# spoke.net
KiCad netlist of a schematic drawn in EAGLE
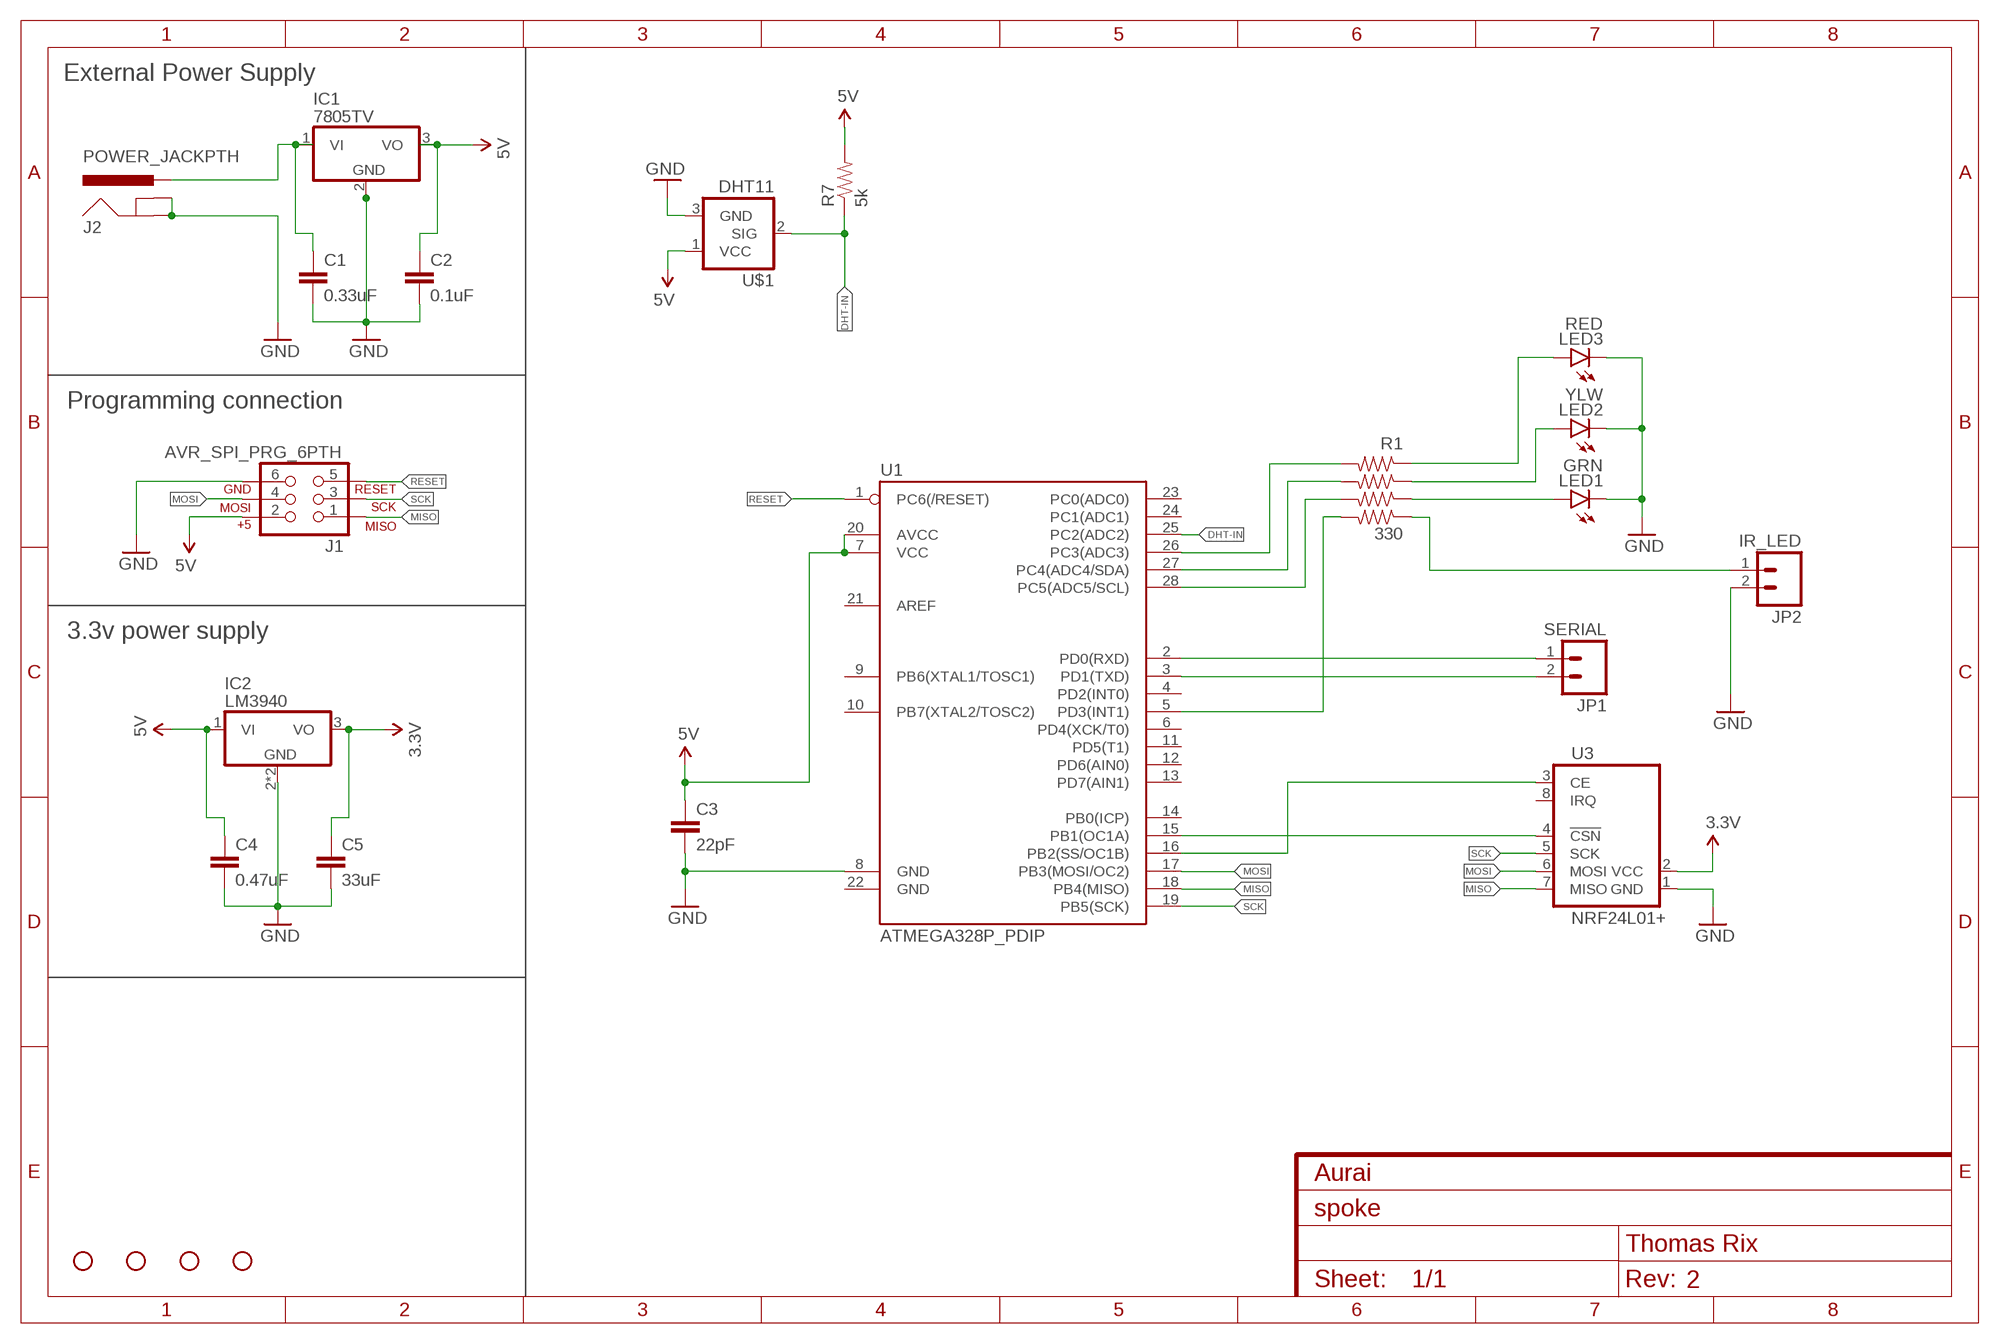
[diagram p0: schematic, sheet 1]

(export (version "E")
  (design (tool "Eeschema 10.0.6"))
  (components
    (comp (ref "C1")
      (value "0.33uF")
      (footprint "eagle-import:0805")
      (libsource (lib "eagle-import") (part "CAP0805"))
    )
    (comp (ref "C2")
      (value "0.1uF")
      (footprint "eagle-import:0805")
      (libsource (lib "eagle-import") (part "CAP0805"))
    )
    (comp (ref "C3")
      (value "22pF")
      (footprint "eagle-import:0805")
      (libsource (lib "eagle-import") (part "SparkFun-Passives_CAP0805"))
    )
    (comp (ref "C4")
      (value "0.47uF")
      (footprint "eagle-import:0805")
      (libsource (lib "eagle-import") (part "CAP0805"))
    )
    (comp (ref "C5")
      (value "33uF")
      (footprint "eagle-import:0805")
      (libsource (lib "eagle-import") (part "CAP0805"))
    )
    (comp (ref "IC1")
      (value "7805TV")
      (footprint "eagle-import:TO220V")
      (libsource (lib "eagle-import") (part "78TV05"))
    )
    (comp (ref "IC2")
      (value "LM3940")
      (footprint "eagle-import:SOT223")
      (libsource (lib "eagle-import") (part "LM3940"))
    )
    (comp (ref "J1")
      (value "AVR_SPI_PRG_6PTH")
      (footprint "eagle-import:2X3")
      (libsource (lib "eagle-import") (part "AVR_SPI_PRG_6PTH"))
    )
    (comp (ref "J2")
      (value "POWER_JACKPTH")
      (footprint "eagle-import:POWER_JACK_PTH")
      (libsource (lib "eagle-import") (part "POWER_JACKPTH"))
    )
    (comp (ref "JP1")
      (value "SERIAL")
      (footprint "eagle-import:1X02")
      (libsource (lib "eagle-import") (part "M02PTH"))
    )
    (comp (ref "JP2")
      (value "IR_LED")
      (footprint "eagle-import:1X02")
      (libsource (lib "eagle-import") (part "M02PTH"))
    )
    (comp (ref "LED1")
      (value "GRN")
      (footprint "eagle-import:LED-1206")
      (libsource (lib "eagle-import") (part "LED1206"))
    )
    (comp (ref "LED2")
      (value "YLW")
      (footprint "eagle-import:LED-1206")
      (libsource (lib "eagle-import") (part "LED1206"))
    )
    (comp (ref "LED3")
      (value "RED")
      (footprint "eagle-import:LED-1206")
      (libsource (lib "eagle-import") (part "LED1206"))
    )
    (comp (ref "R1")
      (value "330")
      (footprint "eagle-import:CRA06S08")
      (libsource (lib "eagle-import") (part "CRA06ES08"))
    )
    (comp (ref "R7")
      (value "5k")
      (footprint "eagle-import:0805")
      (libsource (lib "eagle-import") (part "RESISTOR0805-RES"))
    )
    (comp (ref "STANDOFF1")
      (value "STAND-OFF")
      (footprint "eagle-import:STAND-OFF")
      (libsource (lib "eagle-import") (part "STAND-OFF"))
    )
    (comp (ref "STANDOFF2")
      (value "STAND-OFF")
      (footprint "eagle-import:STAND-OFF")
      (libsource (lib "eagle-import") (part "STAND-OFF"))
    )
    (comp (ref "STANDOFF3")
      (value "STAND-OFF")
      (footprint "eagle-import:STAND-OFF")
      (libsource (lib "eagle-import") (part "STAND-OFF"))
    )
    (comp (ref "STANDOFF4")
      (value "STAND-OFF")
      (footprint "eagle-import:STAND-OFF")
      (libsource (lib "eagle-import") (part "STAND-OFF"))
    )
    (comp (ref "U$1")
      (value "DHT11")
      (footprint "eagle-import:DHT11_HEADER")
      (libsource (lib "eagle-import") (part "DHT11"))
    )
    (comp (ref "U1")
      (value "ATMEGA328P_PDIP")
      (footprint "eagle-import:DIL28-3")
      (libsource (lib "eagle-import") (part "ATMEGA328P_PDIP"))
    )
    (comp (ref "U3")
      (value "NRF24L01+")
      (footprint "eagle-import:NRF24L01_HEADER")
      (libsource (lib "eagle-import") (part "NRF24L01+"))
    )
  )
  (nets
    (net (code "1") (name "3.3V") (class "Default")
      (node (ref "C5") (pin "1") (pinfunction "1_1") (pintype "passive"))
      (node (ref "IC2") (pin "3") (pinfunction "VO_3") (pintype "passive"))
      (node (ref "U3") (pin "2") (pinfunction "VCC_2") (pintype "power_in"))
    )
    (net (code "2") (name "5V") (class "Default")
      (node (ref "C2") (pin "1") (pinfunction "1_1") (pintype "passive"))
      (node (ref "C3") (pin "1") (pinfunction "1_1") (pintype "passive"))
      (node (ref "C4") (pin "1") (pinfunction "1_1") (pintype "passive"))
      (node (ref "IC1") (pin "3") (pinfunction "VO_3") (pintype "passive"))
      (node (ref "IC2") (pin "1") (pinfunction "VI_1") (pintype "input"))
      (node (ref "J1") (pin "2") (pinfunction "2_2") (pintype "passive"))
      (node (ref "R7") (pin "2") (pinfunction "2_2") (pintype "passive"))
      (node (ref "U$1") (pin "1") (pinfunction "VCC_1") (pintype "power_in"))
      (node (ref "U1") (pin "20") (pinfunction "AVCC_20") (pintype "bidirectional"))
      (node (ref "U1") (pin "7") (pinfunction "VCC_7") (pintype "bidirectional"))
    )
    (net (code "3") (name "DHT-IN") (class "Default")
      (node (ref "R7") (pin "1") (pinfunction "1_1") (pintype "passive"))
      (node (ref "U$1") (pin "2") (pinfunction "SIG_2") (pintype "bidirectional"))
      (node (ref "U1") (pin "25") (pinfunction "PC2(ADC2)_25") (pintype "bidirectional"))
    )
    (net (code "4") (name "GND") (class "Default")
      (node (ref "C1") (pin "2") (pinfunction "2_2") (pintype "passive"))
      (node (ref "C2") (pin "2") (pinfunction "2_2") (pintype "passive"))
      (node (ref "C3") (pin "2") (pinfunction "2_2") (pintype "passive"))
      (node (ref "C4") (pin "2") (pinfunction "2_2") (pintype "passive"))
      (node (ref "C5") (pin "2") (pinfunction "2_2") (pintype "passive"))
      (node (ref "IC1") (pin "2") (pinfunction "GND_2") (pintype "passive"))
      (node (ref "IC2") (pin "2") (pinfunction "GND_2") (pintype "power_in"))
      (node (ref "IC2") (pin "4") (pinfunction "GND_4") (pintype "power_in"))
      (node (ref "J1") (pin "6") (pinfunction "6_6") (pintype "passive"))
      (node (ref "J2") (pin "GND") (pinfunction "GND_GND") (pintype "bidirectional"))
      (node (ref "J2") (pin "GNDBREAK") (pinfunction "GNDBREAK_GNDBREAK") (pintype "bidirectional"))
      (node (ref "JP2") (pin "2") (pinfunction "2_2") (pintype "passive"))
      (node (ref "LED1") (pin "C") (pinfunction "C_C") (pintype "passive"))
      (node (ref "LED2") (pin "C") (pinfunction "C_C") (pintype "passive"))
      (node (ref "LED3") (pin "C") (pinfunction "C_C") (pintype "passive"))
      (node (ref "U$1") (pin "3") (pinfunction "GND_3") (pintype "power_in"))
      (node (ref "U1") (pin "8") (pinfunction "GND_8") (pintype "bidirectional"))
      (node (ref "U3") (pin "1") (pinfunction "GND_1") (pintype "power_in"))
    )
    (net (code "5") (name "MISO") (class "Default")
      (node (ref "J1") (pin "1") (pinfunction "1_1") (pintype "passive"))
      (node (ref "U1") (pin "18") (pinfunction "PB4(MISO)_18") (pintype "bidirectional"))
      (node (ref "U3") (pin "7") (pinfunction "MISO_7") (pintype "output"))
    )
    (net (code "6") (name "MOSI") (class "Default")
      (node (ref "J1") (pin "4") (pinfunction "4_4") (pintype "passive"))
      (node (ref "U1") (pin "17") (pinfunction "PB3(MOSI/OC2)_17") (pintype "bidirectional"))
      (node (ref "U3") (pin "6") (pinfunction "MOSI_6") (pintype "input"))
    )
    (net (code "7") (name "Net-(IC1-VI)") (class "Default")
      (node (ref "C1") (pin "1") (pinfunction "1_1") (pintype "passive"))
      (node (ref "IC1") (pin "1") (pinfunction "VI_1") (pintype "input"))
      (node (ref "J2") (pin "PWR") (pinfunction "PWR_PWR") (pintype "bidirectional"))
    )
    (net (code "8") (name "Net-(R1-R1A)") (class "Default")
      (node (ref "LED3") (pin "A") (pinfunction "A_A") (pintype "passive"))
      (node (ref "R1") (pin "1") (pinfunction "R1A_1") (pintype "passive"))
    )
    (net (code "9") (name "Net-(R1-R1B)") (class "Default")
      (node (ref "R1") (pin "8") (pinfunction "R1B_8") (pintype "passive"))
      (node (ref "U1") (pin "26") (pinfunction "PC3(ADC3)_26") (pintype "bidirectional"))
    )
    (net (code "10") (name "Net-(R1-R2A)") (class "Default")
      (node (ref "LED2") (pin "A") (pinfunction "A_A") (pintype "passive"))
      (node (ref "R1") (pin "2") (pinfunction "R2A_2") (pintype "passive"))
    )
    (net (code "11") (name "Net-(R1-R2B)") (class "Default")
      (node (ref "R1") (pin "7") (pinfunction "R2B_7") (pintype "passive"))
      (node (ref "U1") (pin "27") (pinfunction "PC4(ADC4/SDA)_27") (pintype "bidirectional"))
    )
    (net (code "12") (name "Net-(R1-R3A)") (class "Default")
      (node (ref "LED1") (pin "A") (pinfunction "A_A") (pintype "passive"))
      (node (ref "R1") (pin "3") (pinfunction "R3A_3") (pintype "passive"))
    )
    (net (code "13") (name "Net-(R1-R3B)") (class "Default")
      (node (ref "R1") (pin "6") (pinfunction "R3B_6") (pintype "passive"))
      (node (ref "U1") (pin "28") (pinfunction "PC5(ADC5/SCL)_28") (pintype "bidirectional"))
    )
    (net (code "14") (name "Net-(R1-R4A)") (class "Default")
      (node (ref "JP2") (pin "1") (pinfunction "1_1") (pintype "passive"))
      (node (ref "R1") (pin "4") (pinfunction "R4A_4") (pintype "passive"))
    )
    (net (code "15") (name "Net-(R1-R4B)") (class "Default")
      (node (ref "R1") (pin "5") (pinfunction "R4B_5") (pintype "passive"))
      (node (ref "U1") (pin "5") (pinfunction "PD3(INT1)_5") (pintype "bidirectional"))
    )
    (net (code "16") (name "Net-(U1-PB1(OC1A))") (class "Default")
      (node (ref "U1") (pin "15") (pinfunction "PB1(OC1A)_15") (pintype "bidirectional"))
      (node (ref "U3") (pin "4") (pinfunction "~{CSN}_4") (pintype "input"))
    )
    (net (code "17") (name "Net-(U1-PB2(SS{slash}OC1B))") (class "Default")
      (node (ref "U1") (pin "16") (pinfunction "PB2(SS/OC1B)_16") (pintype "bidirectional"))
      (node (ref "U3") (pin "3") (pinfunction "CE_3") (pintype "input"))
    )
    (net (code "18") (name "Net-(U1-PD0(RXD))") (class "Default")
      (node (ref "JP1") (pin "1") (pinfunction "1_1") (pintype "passive"))
      (node (ref "U1") (pin "2") (pinfunction "PD0(RXD)_2") (pintype "bidirectional"))
    )
    (net (code "19") (name "Net-(U1-PD1(TXD))") (class "Default")
      (node (ref "JP1") (pin "2") (pinfunction "2_2") (pintype "passive"))
      (node (ref "U1") (pin "3") (pinfunction "PD1(TXD)_3") (pintype "bidirectional"))
    )
    (net (code "20") (name "RESET") (class "Default")
      (node (ref "J1") (pin "5") (pinfunction "5_5") (pintype "passive"))
      (node (ref "U1") (pin "1") (pinfunction "PC6(/RESET)_1") (pintype "bidirectional"))
    )
    (net (code "21") (name "SCK") (class "Default")
      (node (ref "J1") (pin "3") (pinfunction "3_3") (pintype "passive"))
      (node (ref "U1") (pin "19") (pinfunction "PB5(SCK)_19") (pintype "bidirectional"))
      (node (ref "U3") (pin "5") (pinfunction "SCK_5") (pintype "output"))
    )
    (net (code "22") (name "unconnected-(U1-AREF-Pad21)") (class "Default")
      (node (ref "U1") (pin "21") (pinfunction "AREF_21") (pintype "bidirectional"))
    )
    (net (code "23") (name "unconnected-(U1-GND-Pad22)") (class "Default")
      (node (ref "U1") (pin "22") (pinfunction "GND_22") (pintype "bidirectional"))
    )
    (net (code "24") (name "unconnected-(U1-PB0(ICP)-Pad14)") (class "Default")
      (node (ref "U1") (pin "14") (pinfunction "PB0(ICP)_14") (pintype "bidirectional"))
    )
    (net (code "25") (name "unconnected-(U1-PB6(XTAL1{slash}TOSC1)-Pad9)") (class "Default")
      (node (ref "U1") (pin "9") (pinfunction "PB6(XTAL1/TOSC1)_9") (pintype "bidirectional"))
    )
    (net (code "26") (name "unconnected-(U1-PB7(XTAL2{slash}TOSC2)-Pad10)") (class "Default")
      (node (ref "U1") (pin "10") (pinfunction "PB7(XTAL2/TOSC2)_10") (pintype "bidirectional"))
    )
    (net (code "27") (name "unconnected-(U1-PC0(ADC0)-Pad23)") (class "Default")
      (node (ref "U1") (pin "23") (pinfunction "PC0(ADC0)_23") (pintype "bidirectional"))
    )
    (net (code "28") (name "unconnected-(U1-PC1(ADC1)-Pad24)") (class "Default")
      (node (ref "U1") (pin "24") (pinfunction "PC1(ADC1)_24") (pintype "bidirectional"))
    )
    (net (code "29") (name "unconnected-(U1-PD2(INT0)-Pad4)") (class "Default")
      (node (ref "U1") (pin "4") (pinfunction "PD2(INT0)_4") (pintype "bidirectional"))
    )
    (net (code "30") (name "unconnected-(U1-PD4(XCK{slash}T0)-Pad6)") (class "Default")
      (node (ref "U1") (pin "6") (pinfunction "PD4(XCK/T0)_6") (pintype "bidirectional"))
    )
    (net (code "31") (name "unconnected-(U1-PD5(T1)-Pad11)") (class "Default")
      (node (ref "U1") (pin "11") (pinfunction "PD5(T1)_11") (pintype "bidirectional"))
    )
    (net (code "32") (name "unconnected-(U1-PD6(AIN0)-Pad12)") (class "Default")
      (node (ref "U1") (pin "12") (pinfunction "PD6(AIN0)_12") (pintype "bidirectional"))
    )
    (net (code "33") (name "unconnected-(U1-PD7(AIN1)-Pad13)") (class "Default")
      (node (ref "U1") (pin "13") (pinfunction "PD7(AIN1)_13") (pintype "bidirectional"))
    )
    (net (code "34") (name "unconnected-(U3-IRQ-Pad8)") (class "Default")
      (node (ref "U3") (pin "8") (pinfunction "IRQ_8") (pintype "output"))
    )
  )
)
